# IgnMOSFET.net
KiCad netlist of a schematic drawn in Altium Designer
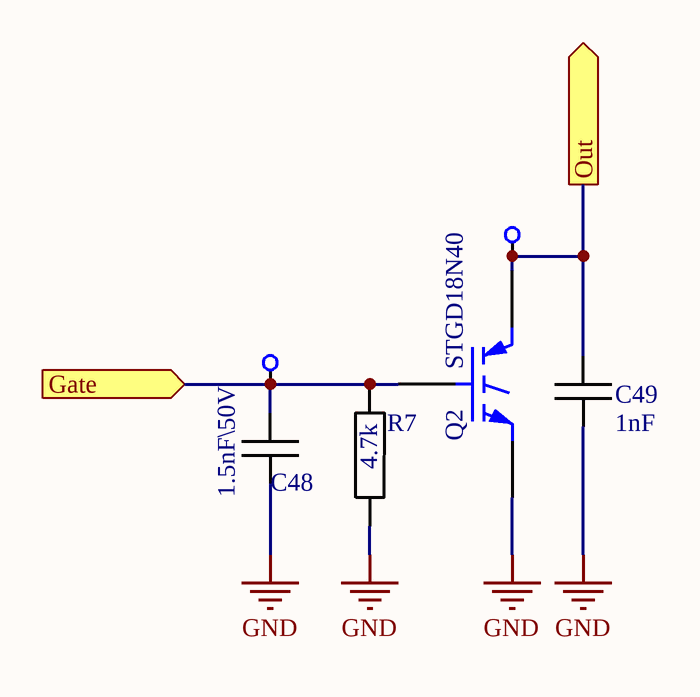
[diagram p0: IgnMOSFET.SchDoc]

(export (version "E")
  (design (tool "Eeschema 10.0.6"))
  (components
    (comp (ref "C48")
      (value "1.5n~{F}50V")
      (footprint "SMD 0603")
      (description "CC0603KRX7R9BB152")
      (libsource (lib "Maks_lib") (part "Capasitor"))
    )
    (comp (ref "C49")
      (value "1nF")
      (footprint "SMD 0603")
      (description "CC0603KRX7R9BB102")
      (libsource (lib "Maks_lib") (part "Capasitor"))
    )
    (comp (ref "Q2")
      (value "STGD18N40")
      (footprint "DPAK228P991X238-3M")
      (description "IGBT Automotive-grade 390 V internally clamped  ESCIS 180 mJ")
      (libsource (lib "Maks_lib") (part "STGD18N40"))
    )
    (comp (ref "R7")
      (value "4.7k")
      (footprint "SMD 0603")
      (description "RC0603FR-074K7L")
      (libsource (lib "Maks_lib") (part "Resistor"))
    )
    (comp (ref "TP29")
      (value "TestPoint")
      (footprint "TESTPOINT")
      (description "testPoint")
      (libsource (lib "Maks_lib") (part "TestPoint"))
    )
    (comp (ref "TP30")
      (value "TestPoint")
      (footprint "TESTPOINT")
      (description "testPoint")
      (libsource (lib "Maks_lib") (part "TestPoint"))
    )
  )
  (nets
    (net (code "1") (name "/Gate") (class "Default")
      (node (ref "C48") (pin "2") (pinfunction "2_2") (pintype "passive"))
      (node (ref "Q2") (pin "1") (pinfunction "G_1") (pintype "passive"))
      (node (ref "R7") (pin "2") (pinfunction "2_2") (pintype "passive"))
      (node (ref "TP29") (pin "0") (pinfunction "0_0") (pintype "passive"))
    )
    (net (code "2") (name "/Out") (class "Default")
      (node (ref "C49") (pin "2") (pinfunction "2_2") (pintype "passive"))
      (node (ref "Q2") (pin "4") (pinfunction "C_4") (pintype "passive"))
      (node (ref "TP30") (pin "0") (pinfunction "0_0") (pintype "passive"))
    )
    (net (code "3") (name "GND") (class "Default")
      (node (ref "C48") (pin "1") (pinfunction "1_1") (pintype "passive"))
      (node (ref "C49") (pin "1") (pinfunction "1_1") (pintype "passive"))
      (node (ref "Q2") (pin "3") (pinfunction "E_3") (pintype "passive"))
      (node (ref "R7") (pin "1") (pinfunction "1_1") (pintype "passive"))
    )
  )
)
